# STM32.net
KiCad netlist of a schematic drawn in Altium Designer
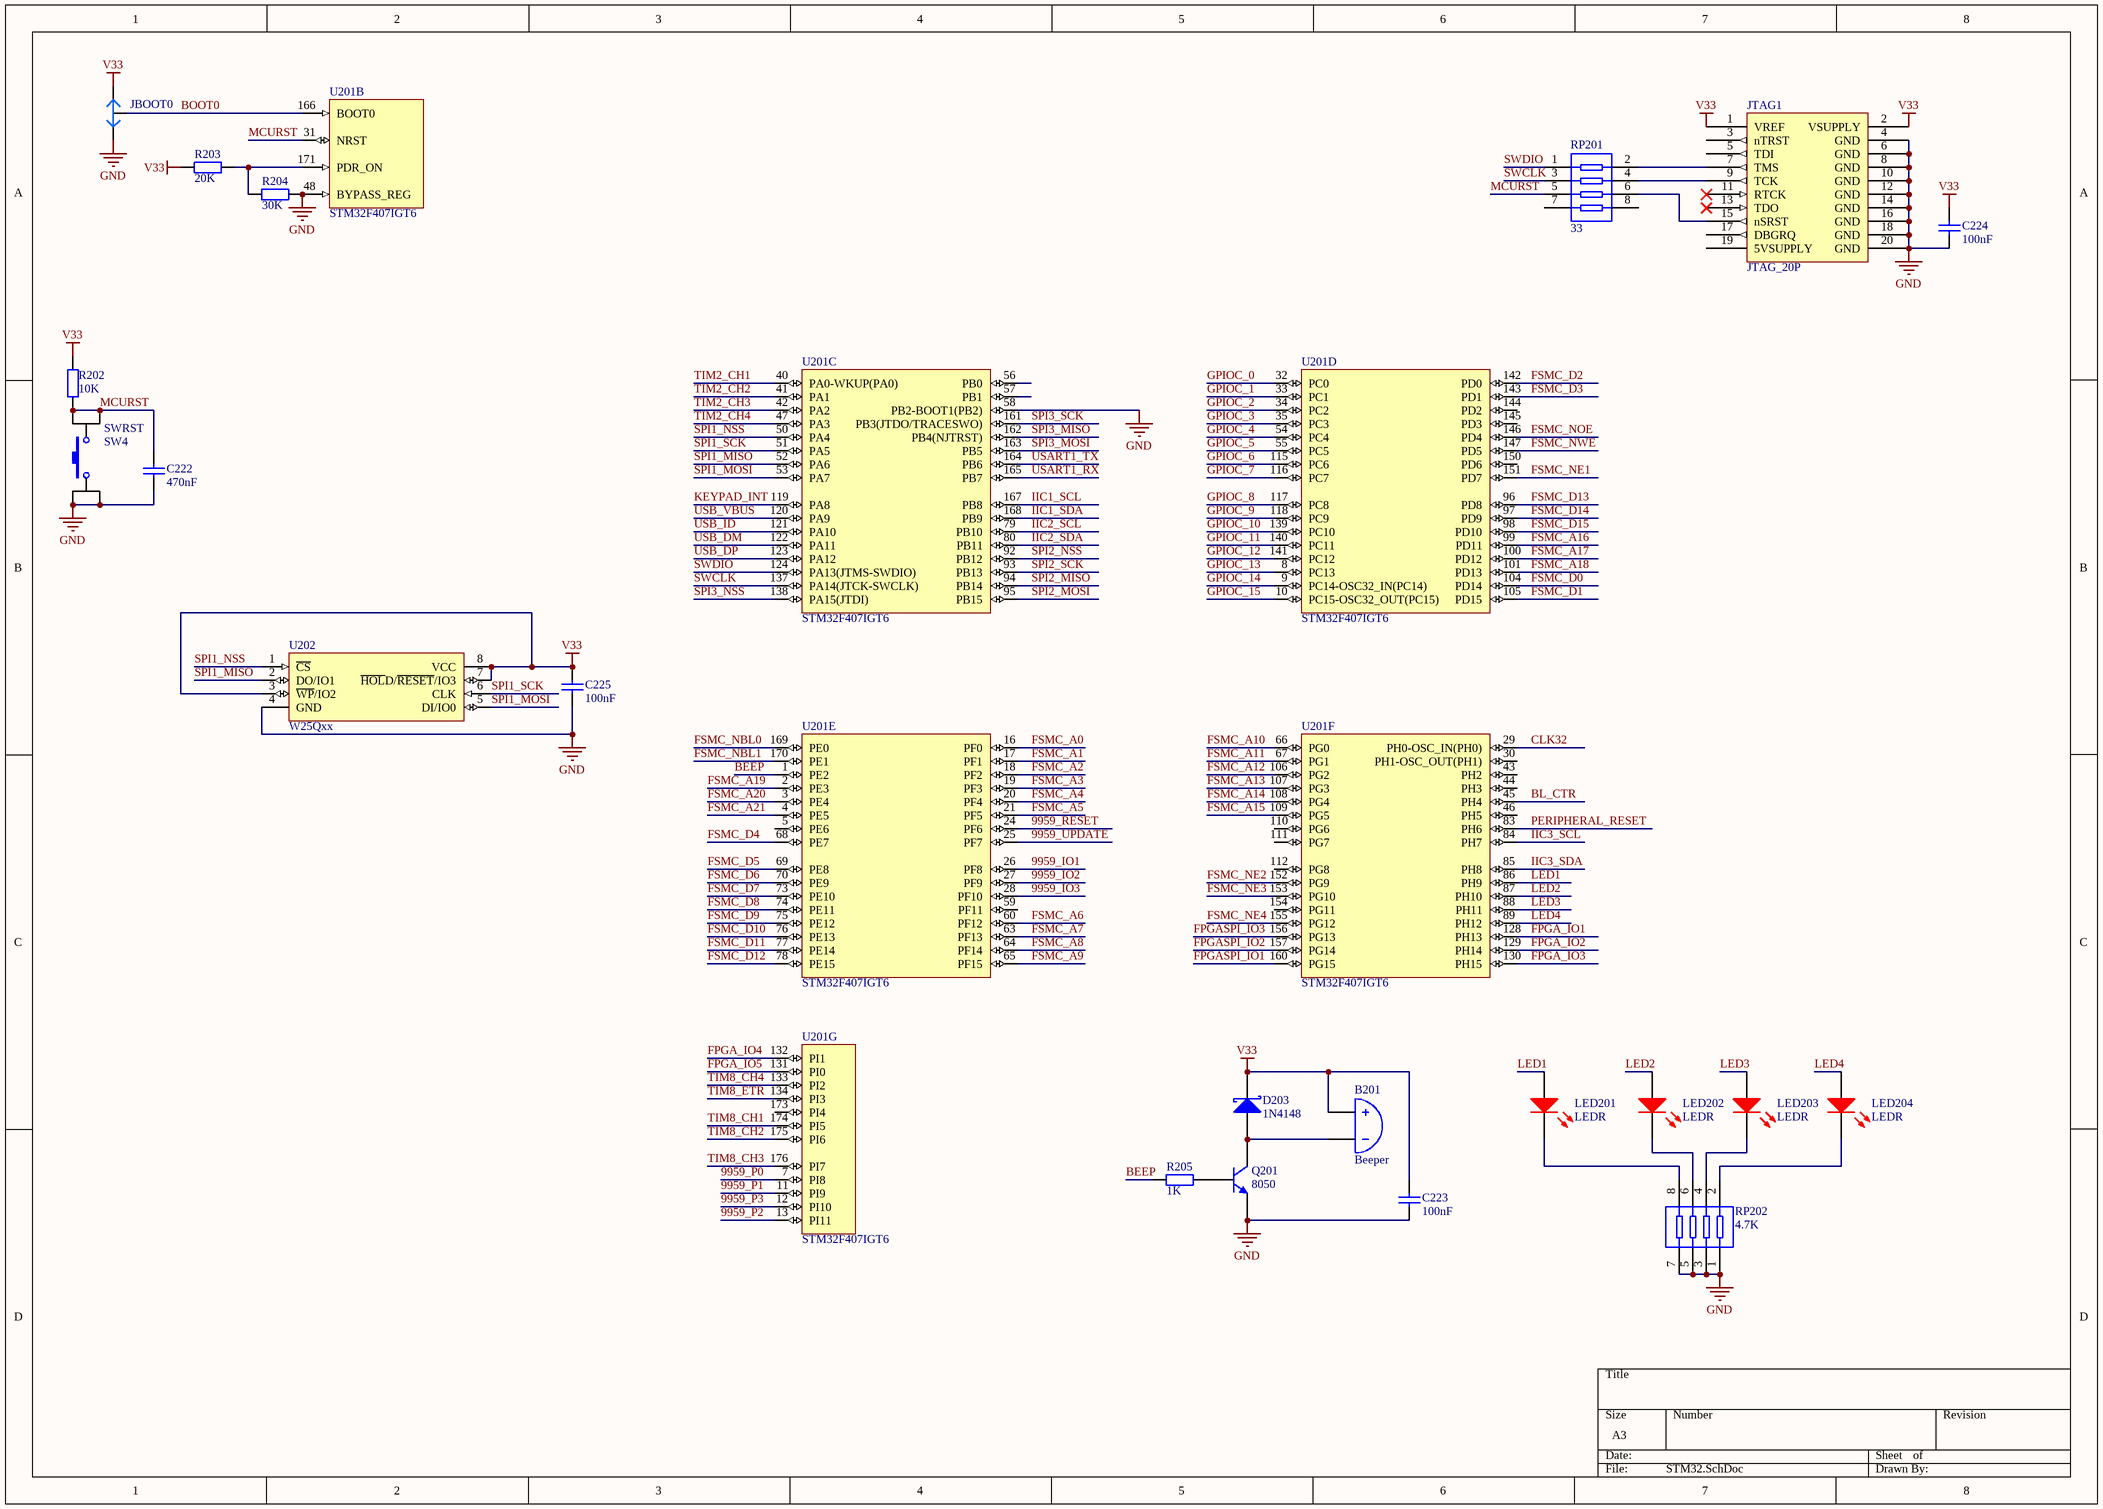
[diagram p0: STM32.SchDoc]

(export (version "E")
  (design (tool "Eeschema 10.0.6"))
  (components
    (comp (ref "B201") (value "Beeper") (footprint "BEEPER") (libsource (lib "Misc") (part "Beeper")))
    (comp (ref "C222")
      (value "470nF")
      (footprint "0603C")
      (description "MLCC")
      (libsource (lib "Misc") (part "MLCC"))
    )
    (comp (ref "C223")
      (value "100nF")
      (footprint "0603C")
      (description "MLCC")
      (libsource (lib "Misc") (part "MLCC"))
    )
    (comp (ref "C224")
      (value "100nF")
      (footprint "0805C")
      (description "MLCC")
      (libsource (lib "Misc") (part "MLCC"))
    )
    (comp (ref "C225")
      (value "100nF")
      (footprint "0603C")
      (description "MLCC")
      (libsource (lib "Misc") (part "MLCC"))
    )
    (comp (ref "D203")
      (value "1N4148")
      (footprint "SOD323")
      (description "Small signal didoe")
      (libsource (lib "Misc") (part "1N4148"))
    )
    (comp (ref "JBOOT0")
      (value "Switch_2Ch_Line")
      (footprint "SWITCH_2CH_LINE")
      (libsource (lib "Misc") (part "Switch_2Ch_Line"))
    )
    (comp (ref "JTAG1")
      (value "JTAG_20P")
      (footprint "JTAG20")
      (description "20 pin JTAG port")
      (libsource (lib "JTAG") (part "JTAG_20P"))
    )
    (comp (ref "LED201")
      (value "LEDR")
      (footprint "LED1206R")
      (description "RED LED")
      (libsource (lib "Misc") (part "LEDR"))
    )
    (comp (ref "LED202")
      (value "LEDR")
      (footprint "LED1206R")
      (description "RED LED")
      (libsource (lib "Misc") (part "LEDR"))
    )
    (comp (ref "LED203")
      (value "LEDR")
      (footprint "LED1206R")
      (description "RED LED")
      (libsource (lib "Misc") (part "LEDR"))
    )
    (comp (ref "LED204")
      (value "LEDR")
      (footprint "LED1206R")
      (description "RED LED")
      (libsource (lib "Misc") (part "LEDR"))
    )
    (comp (ref "Q201")
      (value "8050")
      (footprint "SOT-23")
      (description "NPN Bipolar Transistor")
      (libsource (lib "Misc") (part "8050"))
    )
    (comp (ref "R202")
      (value "10K")
      (footprint "0603R")
      (description "Resistor")
      (libsource (lib "") (part "Resistor_1"))
    )
    (comp (ref "R203")
      (value "20K")
      (footprint "0603R")
      (description "Resistor")
      (libsource (lib "Misc") (part "Resistor"))
    )
    (comp (ref "R204")
      (value "30K")
      (footprint "0603R")
      (description "Resistor")
      (libsource (lib "Misc") (part "Resistor"))
    )
    (comp (ref "R205")
      (value "1K")
      (footprint "0603R")
      (description "Resistor")
      (libsource (lib "Misc") (part "Resistor"))
    )
    (comp (ref "RP201")
      (value "33")
      (footprint "8P4R_0603")
      (description "Isolated Resistor Network")
      (fields (field (name "Comment") "Res Pack"))
      (libsource (lib "Misc") (part "Res Pack"))
    )
    (comp (ref "RP202")
      (value "4.7K")
      (footprint "8P4R_0603")
      (description "Isolated Resistor Network")
      (fields (field (name "Comment") "Res Pack"))
      (libsource (lib "Misc") (part "Res Pack"))
    )
    (comp (ref "SWRST")
      (value "SW4")
      (footprint "SW-0606")
      (description "Switch")
      (libsource (lib "Switch") (part "SW4"))
    )
    (comp (ref "U201")
      (value "STM32F407IGT6")
      (footprint "STM-LQFP176_N")
      (fields (field (name "MANUFACTURER") "STMicroelectronics"))
      (libsource (lib "STMicroelectronics STM32 F4") (part "STM32F407IGT6"))
    )
    (comp (ref "U202")
      (value "W25Qxx")
      (footprint "W25Qxx")
      (description "3V SERIAL FLASH MEMORY WITH DUAL/QUAD SPI & QPI")
      (libsource (lib "W25Qxx") (part "W25Qxx"))
    )
  )
  (nets
    (net (code "1") (name "/9959_IO1") (class "Default")
      (node (ref "U201") (pin "26") (pinfunction "PF8_26") (pintype "bidirectional"))
    )
    (net (code "2") (name "/9959_IO2") (class "Default")
      (node (ref "U201") (pin "27") (pinfunction "PF9_27") (pintype "bidirectional"))
    )
    (net (code "3") (name "/9959_IO3") (class "Default")
      (node (ref "U201") (pin "28") (pinfunction "PF10_28") (pintype "bidirectional"))
    )
    (net (code "4") (name "/9959_P0") (class "Default")
      (node (ref "U201") (pin "7") (pinfunction "PI8_7") (pintype "bidirectional"))
    )
    (net (code "5") (name "/9959_P1") (class "Default")
      (node (ref "U201") (pin "11") (pinfunction "PI9_11") (pintype "bidirectional"))
    )
    (net (code "6") (name "/9959_P2") (class "Default")
      (node (ref "U201") (pin "13") (pinfunction "PI11_13") (pintype "bidirectional"))
    )
    (net (code "7") (name "/9959_P3") (class "Default")
      (node (ref "U201") (pin "12") (pinfunction "PI10_12") (pintype "bidirectional"))
    )
    (net (code "8") (name "/9959_RESET") (class "Default")
      (node (ref "U201") (pin "24") (pinfunction "PF6_24") (pintype "bidirectional"))
    )
    (net (code "9") (name "/9959_UPDATE") (class "Default")
      (node (ref "U201") (pin "25") (pinfunction "PF7_25") (pintype "bidirectional"))
    )
    (net (code "10") (name "/BEEP") (class "Default")
      (node (ref "R205") (pin "1") (pinfunction "1_1") (pintype "passive"))
      (node (ref "U201") (pin "1") (pinfunction "PE2_1") (pintype "bidirectional"))
    )
    (net (code "11") (name "/BL_CTR") (class "Default")
      (node (ref "U201") (pin "45") (pinfunction "PH4_45") (pintype "bidirectional"))
    )
    (net (code "12") (name "/BOOT0") (class "Default")
      (node (ref "JBOOT0") (pin "1") (pintype "passive"))
      (node (ref "U201") (pin "166") (pinfunction "BOOT0_166") (pintype "input"))
    )
    (net (code "13") (name "/CLK32") (class "Default")
      (node (ref "U201") (pin "29") (pinfunction "PH0-OSC_IN(PH0)_29") (pintype "bidirectional"))
    )
    (net (code "14") (name "/FPGASPI_IO1") (class "Default")
      (node (ref "U201") (pin "160") (pinfunction "PG15_160") (pintype "bidirectional"))
    )
    (net (code "15") (name "/FPGASPI_IO2") (class "Default")
      (node (ref "U201") (pin "157") (pinfunction "PG14_157") (pintype "bidirectional"))
    )
    (net (code "16") (name "/FPGASPI_IO3") (class "Default")
      (node (ref "U201") (pin "156") (pinfunction "PG13_156") (pintype "bidirectional"))
    )
    (net (code "17") (name "/FPGA_IO1") (class "Default")
      (node (ref "U201") (pin "128") (pinfunction "PH13_128") (pintype "bidirectional"))
    )
    (net (code "18") (name "/FPGA_IO2") (class "Default")
      (node (ref "U201") (pin "129") (pinfunction "PH14_129") (pintype "bidirectional"))
    )
    (net (code "19") (name "/FPGA_IO3") (class "Default")
      (node (ref "U201") (pin "130") (pinfunction "PH15_130") (pintype "bidirectional"))
    )
    (net (code "20") (name "/FPGA_IO4") (class "Default")
      (node (ref "U201") (pin "132") (pinfunction "PI1_132") (pintype "bidirectional"))
    )
    (net (code "21") (name "/FPGA_IO5") (class "Default")
      (node (ref "U201") (pin "131") (pinfunction "PI0_131") (pintype "bidirectional"))
    )
    (net (code "22") (name "/FSMC_A0") (class "Default")
      (node (ref "U201") (pin "16") (pinfunction "PF0_16") (pintype "bidirectional"))
    )
    (net (code "23") (name "/FSMC_A1") (class "Default")
      (node (ref "U201") (pin "17") (pinfunction "PF1_17") (pintype "bidirectional"))
    )
    (net (code "24") (name "/FSMC_A2") (class "Default")
      (node (ref "U201") (pin "18") (pinfunction "PF2_18") (pintype "bidirectional"))
    )
    (net (code "25") (name "/FSMC_A3") (class "Default")
      (node (ref "U201") (pin "19") (pinfunction "PF3_19") (pintype "bidirectional"))
    )
    (net (code "26") (name "/FSMC_A4") (class "Default")
      (node (ref "U201") (pin "20") (pinfunction "PF4_20") (pintype "bidirectional"))
    )
    (net (code "27") (name "/FSMC_A5") (class "Default")
      (node (ref "U201") (pin "21") (pinfunction "PF5_21") (pintype "bidirectional"))
    )
    (net (code "28") (name "/FSMC_A6") (class "Default")
      (node (ref "U201") (pin "60") (pinfunction "PF12_60") (pintype "bidirectional"))
    )
    (net (code "29") (name "/FSMC_A7") (class "Default")
      (node (ref "U201") (pin "63") (pinfunction "PF13_63") (pintype "bidirectional"))
    )
    (net (code "30") (name "/FSMC_A8") (class "Default")
      (node (ref "U201") (pin "64") (pinfunction "PF14_64") (pintype "bidirectional"))
    )
    (net (code "31") (name "/FSMC_A9") (class "Default")
      (node (ref "U201") (pin "65") (pinfunction "PF15_65") (pintype "bidirectional"))
    )
    (net (code "32") (name "/FSMC_A10") (class "Default")
      (node (ref "U201") (pin "66") (pinfunction "PG0_66") (pintype "bidirectional"))
    )
    (net (code "33") (name "/FSMC_A11") (class "Default")
      (node (ref "U201") (pin "67") (pinfunction "PG1_67") (pintype "bidirectional"))
    )
    (net (code "34") (name "/FSMC_A12") (class "Default")
      (node (ref "U201") (pin "106") (pinfunction "PG2_106") (pintype "bidirectional"))
    )
    (net (code "35") (name "/FSMC_A13") (class "Default")
      (node (ref "U201") (pin "107") (pinfunction "PG3_107") (pintype "bidirectional"))
    )
    (net (code "36") (name "/FSMC_A14") (class "Default")
      (node (ref "U201") (pin "108") (pinfunction "PG4_108") (pintype "bidirectional"))
    )
    (net (code "37") (name "/FSMC_A15") (class "Default")
      (node (ref "U201") (pin "109") (pinfunction "PG5_109") (pintype "bidirectional"))
    )
    (net (code "38") (name "/FSMC_A16") (class "Default")
      (node (ref "U201") (pin "99") (pinfunction "PD11_99") (pintype "bidirectional"))
    )
    (net (code "39") (name "/FSMC_A17") (class "Default")
      (node (ref "U201") (pin "100") (pinfunction "PD12_100") (pintype "bidirectional"))
    )
    (net (code "40") (name "/FSMC_A18") (class "Default")
      (node (ref "U201") (pin "101") (pinfunction "PD13_101") (pintype "bidirectional"))
    )
    (net (code "41") (name "/FSMC_A19") (class "Default")
      (node (ref "U201") (pin "2") (pinfunction "PE3_2") (pintype "bidirectional"))
    )
    (net (code "42") (name "/FSMC_A20") (class "Default")
      (node (ref "U201") (pin "3") (pinfunction "PE4_3") (pintype "bidirectional"))
    )
    (net (code "43") (name "/FSMC_A21") (class "Default")
      (node (ref "U201") (pin "4") (pinfunction "PE5_4") (pintype "bidirectional"))
    )
    (net (code "44") (name "/FSMC_D0") (class "Default")
      (node (ref "U201") (pin "104") (pinfunction "PD14_104") (pintype "bidirectional"))
    )
    (net (code "45") (name "/FSMC_D1") (class "Default")
      (node (ref "U201") (pin "105") (pinfunction "PD15_105") (pintype "bidirectional"))
    )
    (net (code "46") (name "/FSMC_D2") (class "Default")
      (node (ref "U201") (pin "142") (pinfunction "PD0_142") (pintype "bidirectional"))
    )
    (net (code "47") (name "/FSMC_D3") (class "Default")
      (node (ref "U201") (pin "143") (pinfunction "PD1_143") (pintype "bidirectional"))
    )
    (net (code "48") (name "/FSMC_D4") (class "Default")
      (node (ref "U201") (pin "68") (pinfunction "PE7_68") (pintype "bidirectional"))
    )
    (net (code "49") (name "/FSMC_D5") (class "Default")
      (node (ref "U201") (pin "69") (pinfunction "PE8_69") (pintype "bidirectional"))
    )
    (net (code "50") (name "/FSMC_D6") (class "Default")
      (node (ref "U201") (pin "70") (pinfunction "PE9_70") (pintype "bidirectional"))
    )
    (net (code "51") (name "/FSMC_D7") (class "Default")
      (node (ref "U201") (pin "73") (pinfunction "PE10_73") (pintype "bidirectional"))
    )
    (net (code "52") (name "/FSMC_D8") (class "Default")
      (node (ref "U201") (pin "74") (pinfunction "PE11_74") (pintype "bidirectional"))
    )
    (net (code "53") (name "/FSMC_D9") (class "Default")
      (node (ref "U201") (pin "75") (pinfunction "PE12_75") (pintype "bidirectional"))
    )
    (net (code "54") (name "/FSMC_D10") (class "Default")
      (node (ref "U201") (pin "76") (pinfunction "PE13_76") (pintype "bidirectional"))
    )
    (net (code "55") (name "/FSMC_D11") (class "Default")
      (node (ref "U201") (pin "77") (pinfunction "PE14_77") (pintype "bidirectional"))
    )
    (net (code "56") (name "/FSMC_D12") (class "Default")
      (node (ref "U201") (pin "78") (pinfunction "PE15_78") (pintype "bidirectional"))
    )
    (net (code "57") (name "/FSMC_D13") (class "Default")
      (node (ref "U201") (pin "96") (pinfunction "PD8_96") (pintype "bidirectional"))
    )
    (net (code "58") (name "/FSMC_D14") (class "Default")
      (node (ref "U201") (pin "97") (pinfunction "PD9_97") (pintype "bidirectional"))
    )
    (net (code "59") (name "/FSMC_D15") (class "Default")
      (node (ref "U201") (pin "98") (pinfunction "PD10_98") (pintype "bidirectional"))
    )
    (net (code "60") (name "/FSMC_NBL0") (class "Default")
      (node (ref "U201") (pin "169") (pinfunction "PE0_169") (pintype "bidirectional"))
    )
    (net (code "61") (name "/FSMC_NBL1") (class "Default")
      (node (ref "U201") (pin "170") (pinfunction "PE1_170") (pintype "bidirectional"))
    )
    (net (code "62") (name "/FSMC_NE1") (class "Default")
      (node (ref "U201") (pin "151") (pinfunction "PD7_151") (pintype "bidirectional"))
    )
    (net (code "63") (name "/FSMC_NE2") (class "Default")
      (node (ref "U201") (pin "152") (pinfunction "PG9_152") (pintype "bidirectional"))
    )
    (net (code "64") (name "/FSMC_NE3") (class "Default")
      (node (ref "U201") (pin "153") (pinfunction "PG10_153") (pintype "bidirectional"))
    )
    (net (code "65") (name "/FSMC_NE4") (class "Default")
      (node (ref "U201") (pin "155") (pinfunction "PG12_155") (pintype "bidirectional"))
    )
    (net (code "66") (name "/FSMC_NOE") (class "Default")
      (node (ref "U201") (pin "146") (pinfunction "PD4_146") (pintype "bidirectional"))
    )
    (net (code "67") (name "/FSMC_NWE") (class "Default")
      (node (ref "U201") (pin "147") (pinfunction "PD5_147") (pintype "bidirectional"))
    )
    (net (code "68") (name "/GPIOC_0") (class "Default")
      (node (ref "U201") (pin "32") (pinfunction "PC0_32") (pintype "bidirectional"))
    )
    (net (code "69") (name "/GPIOC_1") (class "Default")
      (node (ref "U201") (pin "33") (pinfunction "PC1_33") (pintype "bidirectional"))
    )
    (net (code "70") (name "/GPIOC_2") (class "Default")
      (node (ref "U201") (pin "34") (pinfunction "PC2_34") (pintype "bidirectional"))
    )
    (net (code "71") (name "/GPIOC_3") (class "Default")
      (node (ref "U201") (pin "35") (pinfunction "PC3_35") (pintype "bidirectional"))
    )
    (net (code "72") (name "/GPIOC_4") (class "Default")
      (node (ref "U201") (pin "54") (pinfunction "PC4_54") (pintype "bidirectional"))
    )
    (net (code "73") (name "/GPIOC_5") (class "Default")
      (node (ref "U201") (pin "55") (pinfunction "PC5_55") (pintype "bidirectional"))
    )
    (net (code "74") (name "/GPIOC_6") (class "Default")
      (node (ref "U201") (pin "115") (pinfunction "PC6_115") (pintype "bidirectional"))
    )
    (net (code "75") (name "/GPIOC_7") (class "Default")
      (node (ref "U201") (pin "116") (pinfunction "PC7_116") (pintype "bidirectional"))
    )
    (net (code "76") (name "/GPIOC_8") (class "Default")
      (node (ref "U201") (pin "117") (pinfunction "PC8_117") (pintype "bidirectional"))
    )
    (net (code "77") (name "/GPIOC_9") (class "Default")
      (node (ref "U201") (pin "118") (pinfunction "PC9_118") (pintype "bidirectional"))
    )
    (net (code "78") (name "/GPIOC_10") (class "Default")
      (node (ref "U201") (pin "139") (pinfunction "PC10_139") (pintype "bidirectional"))
    )
    (net (code "79") (name "/GPIOC_11") (class "Default")
      (node (ref "U201") (pin "140") (pinfunction "PC11_140") (pintype "bidirectional"))
    )
    (net (code "80") (name "/GPIOC_12") (class "Default")
      (node (ref "U201") (pin "141") (pinfunction "PC12_141") (pintype "bidirectional"))
    )
    (net (code "81") (name "/GPIOC_13") (class "Default")
      (node (ref "U201") (pin "8") (pinfunction "PC13_8") (pintype "bidirectional"))
    )
    (net (code "82") (name "/GPIOC_14") (class "Default")
      (node (ref "U201") (pin "9") (pinfunction "PC14-OSC32_IN(PC14)_9") (pintype "bidirectional"))
    )
    (net (code "83") (name "/GPIOC_15") (class "Default")
      (node (ref "U201") (pin "10") (pinfunction "PC15-OSC32_OUT(PC15)_10") (pintype "bidirectional"))
    )
    (net (code "84") (name "/IIC1_SCL") (class "Default")
      (node (ref "U201") (pin "167") (pinfunction "PB8_167") (pintype "bidirectional"))
    )
    (net (code "85") (name "/IIC1_SDA") (class "Default")
      (node (ref "U201") (pin "168") (pinfunction "PB9_168") (pintype "bidirectional"))
    )
    (net (code "86") (name "/IIC2_SCL") (class "Default")
      (node (ref "U201") (pin "79") (pinfunction "PB10_79") (pintype "bidirectional"))
    )
    (net (code "87") (name "/IIC2_SDA") (class "Default")
      (node (ref "U201") (pin "80") (pinfunction "PB11_80") (pintype "bidirectional"))
    )
    (net (code "88") (name "/IIC3_SCL") (class "Default")
      (node (ref "U201") (pin "84") (pinfunction "PH7_84") (pintype "bidirectional"))
    )
    (net (code "89") (name "/IIC3_SDA") (class "Default")
      (node (ref "U201") (pin "85") (pinfunction "PH8_85") (pintype "bidirectional"))
    )
    (net (code "90") (name "/KEYPAD_INT") (class "Default")
      (node (ref "U201") (pin "119") (pinfunction "PA8_119") (pintype "bidirectional"))
    )
    (net (code "91") (name "/LED1") (class "Default")
      (node (ref "LED201") (pin "1") (pinfunction "A_1") (pintype "passive"))
      (node (ref "U201") (pin "86") (pinfunction "PH9_86") (pintype "bidirectional"))
    )
    (net (code "92") (name "/LED2") (class "Default")
      (node (ref "LED202") (pin "1") (pinfunction "A_1") (pintype "passive"))
      (node (ref "U201") (pin "87") (pinfunction "PH10_87") (pintype "bidirectional"))
    )
    (net (code "93") (name "/LED3") (class "Default")
      (node (ref "LED203") (pin "1") (pinfunction "A_1") (pintype "passive"))
      (node (ref "U201") (pin "88") (pinfunction "PH11_88") (pintype "bidirectional"))
    )
    (net (code "94") (name "/LED4") (class "Default")
      (node (ref "LED204") (pin "1") (pinfunction "A_1") (pintype "passive"))
      (node (ref "U201") (pin "89") (pinfunction "PH12_89") (pintype "bidirectional"))
    )
    (net (code "95") (name "/MCURST") (class "Default")
      (node (ref "C222") (pin "2") (pinfunction "2_2") (pintype "passive"))
      (node (ref "R202") (pin "1") (pinfunction "1_1") (pintype "passive"))
      (node (ref "RP201") (pin "5") (pinfunction "5_5") (pintype "passive"))
      (node (ref "SWRST") (pin "1") (pinfunction "1_1") (pintype "passive"))
      (node (ref "SWRST") (pin "3") (pinfunction "3_3") (pintype "passive"))
      (node (ref "U201") (pin "31") (pinfunction "NRST_31") (pintype "bidirectional"))
    )
    (net (code "96") (name "/PERIPHERAL_RESET") (class "Default")
      (node (ref "U201") (pin "83") (pinfunction "PH6_83") (pintype "bidirectional"))
    )
    (net (code "97") (name "/SPI1_MISO") (class "Default")
      (node (ref "U201") (pin "52") (pinfunction "PA6_52") (pintype "bidirectional"))
      (node (ref "U202") (pin "2") (pinfunction "DO/IO1_2") (pintype "bidirectional"))
    )
    (net (code "98") (name "/SPI1_MOSI") (class "Default")
      (node (ref "U201") (pin "53") (pinfunction "PA7_53") (pintype "bidirectional"))
      (node (ref "U202") (pin "5") (pinfunction "DI/IO0_5") (pintype "bidirectional"))
    )
    (net (code "99") (name "/SPI1_NSS") (class "Default")
      (node (ref "U201") (pin "50") (pinfunction "PA4_50") (pintype "bidirectional"))
      (node (ref "U202") (pin "1") (pinfunction "~{CS}_1") (pintype "input"))
    )
    (net (code "100") (name "/SPI1_SCK") (class "Default")
      (node (ref "U201") (pin "51") (pinfunction "PA5_51") (pintype "bidirectional"))
      (node (ref "U202") (pin "6") (pinfunction "CLK_6") (pintype "input"))
    )
    (net (code "101") (name "/SPI2_MISO") (class "Default")
      (node (ref "U201") (pin "94") (pinfunction "PB14_94") (pintype "bidirectional"))
    )
    (net (code "102") (name "/SPI2_MOSI") (class "Default")
      (node (ref "U201") (pin "95") (pinfunction "PB15_95") (pintype "bidirectional"))
    )
    (net (code "103") (name "/SPI2_NSS") (class "Default")
      (node (ref "U201") (pin "92") (pinfunction "PB12_92") (pintype "bidirectional"))
    )
    (net (code "104") (name "/SPI2_SCK") (class "Default")
      (node (ref "U201") (pin "93") (pinfunction "PB13_93") (pintype "bidirectional"))
    )
    (net (code "105") (name "/SPI3_MISO") (class "Default")
      (node (ref "U201") (pin "162") (pinfunction "PB4(NJTRST)_162") (pintype "bidirectional"))
    )
    (net (code "106") (name "/SPI3_MOSI") (class "Default")
      (node (ref "U201") (pin "163") (pinfunction "PB5_163") (pintype "bidirectional"))
    )
    (net (code "107") (name "/SPI3_NSS") (class "Default")
      (node (ref "U201") (pin "138") (pinfunction "PA15(JTDI)_138") (pintype "bidirectional"))
    )
    (net (code "108") (name "/SPI3_SCK") (class "Default")
      (node (ref "U201") (pin "161") (pinfunction "PB3(JTDO/TRACESWO)_161") (pintype "bidirectional"))
    )
    (net (code "109") (name "/SWCLK") (class "Default")
      (node (ref "RP201") (pin "3") (pinfunction "3_3") (pintype "passive"))
      (node (ref "U201") (pin "137") (pinfunction "PA14(JTCK-SWCLK)_137") (pintype "bidirectional"))
    )
    (net (code "110") (name "/SWDIO") (class "Default")
      (node (ref "RP201") (pin "1") (pinfunction "1_1") (pintype "passive"))
      (node (ref "U201") (pin "124") (pinfunction "PA13(JTMS-SWDIO)_124") (pintype "bidirectional"))
    )
    (net (code "111") (name "/TIM2_CH1") (class "Default")
      (node (ref "U201") (pin "40") (pinfunction "PA0-WKUP(PA0)_40") (pintype "bidirectional"))
    )
    (net (code "112") (name "/TIM2_CH2") (class "Default")
      (node (ref "U201") (pin "41") (pinfunction "PA1_41") (pintype "bidirectional"))
    )
    (net (code "113") (name "/TIM2_CH3") (class "Default")
      (node (ref "U201") (pin "42") (pinfunction "PA2_42") (pintype "bidirectional"))
    )
    (net (code "114") (name "/TIM2_CH4") (class "Default")
      (node (ref "U201") (pin "47") (pinfunction "PA3_47") (pintype "bidirectional"))
    )
    (net (code "115") (name "/TIM8_CH1") (class "Default")
      (node (ref "U201") (pin "174") (pinfunction "PI5_174") (pintype "bidirectional"))
    )
    (net (code "116") (name "/TIM8_CH2") (class "Default")
      (node (ref "U201") (pin "175") (pinfunction "PI6_175") (pintype "bidirectional"))
    )
    (net (code "117") (name "/TIM8_CH3") (class "Default")
      (node (ref "U201") (pin "176") (pinfunction "PI7_176") (pintype "bidirectional"))
    )
    (net (code "118") (name "/TIM8_CH4") (class "Default")
      (node (ref "U201") (pin "133") (pinfunction "PI2_133") (pintype "bidirectional"))
    )
    (net (code "119") (name "/TIM8_ETR") (class "Default")
      (node (ref "U201") (pin "134") (pinfunction "PI3_134") (pintype "bidirectional"))
    )
    (net (code "120") (name "/USART1_RX") (class "Default")
      (node (ref "U201") (pin "165") (pinfunction "PB7_165") (pintype "bidirectional"))
    )
    (net (code "121") (name "/USART1_TX") (class "Default")
      (node (ref "U201") (pin "164") (pinfunction "PB6_164") (pintype "bidirectional"))
    )
    (net (code "122") (name "/USB_DM") (class "Default")
      (node (ref "U201") (pin "122") (pinfunction "PA11_122") (pintype "bidirectional"))
    )
    (net (code "123") (name "/USB_DP") (class "Default")
      (node (ref "U201") (pin "123") (pinfunction "PA12_123") (pintype "bidirectional"))
    )
    (net (code "124") (name "/USB_ID") (class "Default")
      (node (ref "U201") (pin "121") (pinfunction "PA10_121") (pintype "bidirectional"))
    )
    (net (code "125") (name "/USB_VBUS") (class "Default")
      (node (ref "U201") (pin "120") (pinfunction "PA9_120") (pintype "bidirectional"))
    )
    (net (code "126") (name "GND") (class "Default")
      (node (ref "C222") (pin "1") (pinfunction "1_1") (pintype "passive"))
      (node (ref "C223") (pin "1") (pinfunction "1_1") (pintype "passive"))
      (node (ref "C224") (pin "1") (pinfunction "1_1") (pintype "passive"))
      (node (ref "C225") (pin "1") (pinfunction "1_1") (pintype "passive"))
      (node (ref "JBOOT0") (pin "3") (pintype "passive"))
      (node (ref "JTAG1") (pin "10") (pinfunction "GND_10") (pintype "power_in"))
      (node (ref "JTAG1") (pin "12") (pinfunction "GND_12") (pintype "power_in"))
      (node (ref "JTAG1") (pin "14") (pinfunction "GND_14") (pintype "power_in"))
      (node (ref "JTAG1") (pin "16") (pinfunction "GND_16") (pintype "power_in"))
      (node (ref "JTAG1") (pin "18") (pinfunction "GND_18") (pintype "power_in"))
      (node (ref "JTAG1") (pin "20") (pinfunction "GND_20") (pintype "power_in"))
      (node (ref "JTAG1") (pin "4") (pinfunction "GND_4") (pintype "power_in"))
      (node (ref "JTAG1") (pin "6") (pinfunction "GND_6") (pintype "power_in"))
      (node (ref "JTAG1") (pin "8") (pinfunction "GND_8") (pintype "power_in"))
      (node (ref "Q201") (pin "2") (pinfunction "E_2") (pintype "passive"))
      (node (ref "R204") (pin "2") (pinfunction "2_2") (pintype "passive"))
      (node (ref "RP202") (pin "1") (pinfunction "1_1") (pintype "passive"))
      (node (ref "RP202") (pin "3") (pinfunction "3_3") (pintype "passive"))
      (node (ref "RP202") (pin "5") (pinfunction "5_5") (pintype "passive"))
      (node (ref "RP202") (pin "7") (pinfunction "7_7") (pintype "passive"))
      (node (ref "SWRST") (pin "2") (pinfunction "2_2") (pintype "passive"))
      (node (ref "SWRST") (pin "4") (pinfunction "4_4") (pintype "passive"))
      (node (ref "U201") (pin "48") (pinfunction "BYPASS_REG_48") (pintype "input"))
      (node (ref "U201") (pin "58") (pinfunction "PB2-BOOT1(PB2)_58") (pintype "bidirectional"))
      (node (ref "U202") (pin "4") (pinfunction "GND_4") (pintype "power_in"))
    )
    (net (code "127") (name "Net-(B201-B)") (class "Default")
      (node (ref "B201") (pin "2") (pinfunction "B_2") (pintype "passive"))
      (node (ref "D203") (pin "1") (pinfunction "A_1") (pintype "passive"))
      (node (ref "Q201") (pin "3") (pinfunction "C_3") (pintype "passive"))
    )
    (net (code "128") (name "Net-(JTAG1-TCK)") (class "Default")
      (node (ref "JTAG1") (pin "9") (pinfunction "TCK_9") (pintype "output"))
      (node (ref "RP201") (pin "4") (pinfunction "4_4") (pintype "passive"))
    )
    (net (code "129") (name "Net-(JTAG1-TMS)") (class "Default")
      (node (ref "JTAG1") (pin "7") (pinfunction "TMS_7") (pintype "output"))
      (node (ref "RP201") (pin "2") (pinfunction "2_2") (pintype "passive"))
    )
    (net (code "130") (name "Net-(JTAG1-nSRST)") (class "Default")
      (node (ref "JTAG1") (pin "15") (pinfunction "nSRST_15") (pintype "output"))
      (node (ref "RP201") (pin "6") (pinfunction "6_6") (pintype "passive"))
    )
    (net (code "131") (name "Net-(LED201-K)") (class "Default")
      (node (ref "LED201") (pin "2") (pinfunction "K_2") (pintype "passive"))
      (node (ref "RP202") (pin "8") (pinfunction "8_8") (pintype "passive"))
    )
    (net (code "132") (name "Net-(LED202-K)") (class "Default")
      (node (ref "LED202") (pin "2") (pinfunction "K_2") (pintype "passive"))
      (node (ref "RP202") (pin "6") (pinfunction "6_6") (pintype "passive"))
    )
    (net (code "133") (name "Net-(LED203-K)") (class "Default")
      (node (ref "LED203") (pin "2") (pinfunction "K_2") (pintype "passive"))
      (node (ref "RP202") (pin "4") (pinfunction "4_4") (pintype "passive"))
    )
    (net (code "134") (name "Net-(LED204-K)") (class "Default")
      (node (ref "LED204") (pin "2") (pinfunction "K_2") (pintype "passive"))
      (node (ref "RP202") (pin "2") (pinfunction "2_2") (pintype "passive"))
    )
    (net (code "135") (name "Net-(Q201-B)") (class "Default")
      (node (ref "Q201") (pin "1") (pinfunction "B_1") (pintype "passive"))
      (node (ref "R205") (pin "2") (pinfunction "2_2") (pintype "passive"))
    )
    (net (code "136") (name "Net-(U201B-PDR_ON)") (class "Default")
      (node (ref "R203") (pin "2") (pinfunction "2_2") (pintype "passive"))
      (node (ref "R204") (pin "1") (pinfunction "1_1") (pintype "passive"))
      (node (ref "U201") (pin "171") (pinfunction "PDR_ON_171") (pintype "input"))
    )
    (net (code "137") (name "V33") (class "Default")
      (node (ref "B201") (pin "1") (pinfunction "A_1") (pintype "passive"))
      (node (ref "C223") (pin "2") (pinfunction "2_2") (pintype "passive"))
      (node (ref "C224") (pin "2") (pinfunction "2_2") (pintype "passive"))
      (node (ref "C225") (pin "2") (pinfunction "2_2") (pintype "passive"))
      (node (ref "D203") (pin "2") (pinfunction "K_2") (pintype "passive"))
      (node (ref "JBOOT0") (pin "2") (pintype "passive"))
      (node (ref "JTAG1") (pin "1") (pinfunction "VREF_1") (pintype "power_in"))
      (node (ref "JTAG1") (pin "2") (pinfunction "VSUPPLY_2") (pintype "power_in"))
      (node (ref "R202") (pin "2") (pinfunction "2_2") (pintype "passive"))
      (node (ref "R203") (pin "1") (pinfunction "1_1") (pintype "passive"))
      (node (ref "U202") (pin "3") (pinfunction "~{WP}/IO2_3") (pintype "bidirectional"))
      (node (ref "U202") (pin "7") (pinfunction "~{HOL}D/~{RESET}/IO3_7") (pintype "bidirectional"))
      (node (ref "U202") (pin "8") (pinfunction "VCC_8") (pintype "power_in"))
    )
    (net (code "138") (name "unconnected-(JTAG1-5VSUPPLY-Pad19)") (class "Default")
      (node (ref "JTAG1") (pin "19") (pinfunction "5VSUPPLY_19") (pintype "power_in"))
    )
    (net (code "139") (name "unconnected-(JTAG1-DBGRQ-Pad17)") (class "Default")
      (node (ref "JTAG1") (pin "17") (pinfunction "DBGRQ_17") (pintype "output"))
    )
    (net (code "140") (name "unconnected-(JTAG1-RTCK-Pad11)") (class "Default")
      (node (ref "JTAG1") (pin "11") (pinfunction "RTCK_11") (pintype "input+no_connect"))
    )
    (net (code "141") (name "unconnected-(JTAG1-TDI-Pad5)") (class "Default")
      (node (ref "JTAG1") (pin "5") (pinfunction "TDI_5") (pintype "output"))
    )
    (net (code "142") (name "unconnected-(JTAG1-TDO-Pad13)") (class "Default")
      (node (ref "JTAG1") (pin "13") (pinfunction "TDO_13") (pintype "input+no_connect"))
    )
    (net (code "143") (name "unconnected-(JTAG1-nTRST-Pad3)") (class "Default")
      (node (ref "JTAG1") (pin "3") (pinfunction "nTRST_3") (pintype "output"))
    )
    (net (code "144") (name "unconnected-(RP201-Pad7)") (class "Default")
      (node (ref "RP201") (pin "7") (pinfunction "7_7") (pintype "passive"))
    )
    (net (code "145") (name "unconnected-(RP201-Pad8)") (class "Default")
      (node (ref "RP201") (pin "8") (pinfunction "8_8") (pintype "passive"))
    )
    (net (code "146") (name "unconnected-(U201C-PB0-Pad56)") (class "Default")
      (node (ref "U201") (pin "56") (pinfunction "PB0_56") (pintype "bidirectional"))
    )
    (net (code "147") (name "unconnected-(U201C-PB1-Pad57)") (class "Default")
      (node (ref "U201") (pin "57") (pinfunction "PB1_57") (pintype "bidirectional"))
    )
    (net (code "148") (name "unconnected-(U201D-PD2-Pad144)") (class "Default")
      (node (ref "U201") (pin "144") (pinfunction "PD2_144") (pintype "bidirectional"))
    )
    (net (code "149") (name "unconnected-(U201D-PD3-Pad145)") (class "Default")
      (node (ref "U201") (pin "145") (pinfunction "PD3_145") (pintype "bidirectional"))
    )
    (net (code "150") (name "unconnected-(U201D-PD6-Pad150)") (class "Default")
      (node (ref "U201") (pin "150") (pinfunction "PD6_150") (pintype "bidirectional"))
    )
    (net (code "151") (name "unconnected-(U201E-PE6-Pad5)") (class "Default")
      (node (ref "U201") (pin "5") (pinfunction "PE6_5") (pintype "bidirectional"))
    )
    (net (code "152") (name "unconnected-(U201E-PF11-Pad59)") (class "Default")
      (node (ref "U201") (pin "59") (pinfunction "PF11_59") (pintype "bidirectional"))
    )
    (net (code "153") (name "unconnected-(U201F-PG6-Pad110)") (class "Default")
      (node (ref "U201") (pin "110") (pinfunction "PG6_110") (pintype "bidirectional"))
    )
    (net (code "154") (name "unconnected-(U201F-PG7-Pad111)") (class "Default")
      (node (ref "U201") (pin "111") (pinfunction "PG7_111") (pintype "bidirectional"))
    )
    (net (code "155") (name "unconnected-(U201F-PG8-Pad112)") (class "Default")
      (node (ref "U201") (pin "112") (pinfunction "PG8_112") (pintype "bidirectional"))
    )
    (net (code "156") (name "unconnected-(U201F-PG11-Pad154)") (class "Default")
      (node (ref "U201") (pin "154") (pinfunction "PG11_154") (pintype "bidirectional"))
    )
    (net (code "157") (name "unconnected-(U201F-PH1-OSC_OUT(PH1)-Pad30)") (class "Default")
      (node (ref "U201") (pin "30") (pinfunction "PH1-OSC_OUT(PH1)_30") (pintype "bidirectional"))
    )
    (net (code "158") (name "unconnected-(U201F-PH2-Pad43)") (class "Default")
      (node (ref "U201") (pin "43") (pinfunction "PH2_43") (pintype "bidirectional"))
    )
    (net (code "159") (name "unconnected-(U201F-PH3-Pad44)") (class "Default")
      (node (ref "U201") (pin "44") (pinfunction "PH3_44") (pintype "bidirectional"))
    )
    (net (code "160") (name "unconnected-(U201F-PH5-Pad46)") (class "Default")
      (node (ref "U201") (pin "46") (pinfunction "PH5_46") (pintype "bidirectional"))
    )
    (net (code "161") (name "unconnected-(U201G-PI4-Pad173)") (class "Default")
      (node (ref "U201") (pin "173") (pinfunction "PI4_173") (pintype "bidirectional"))
    )
  )
)
